# main_cj125.net
KiCad netlist of a schematic drawn in EAGLE
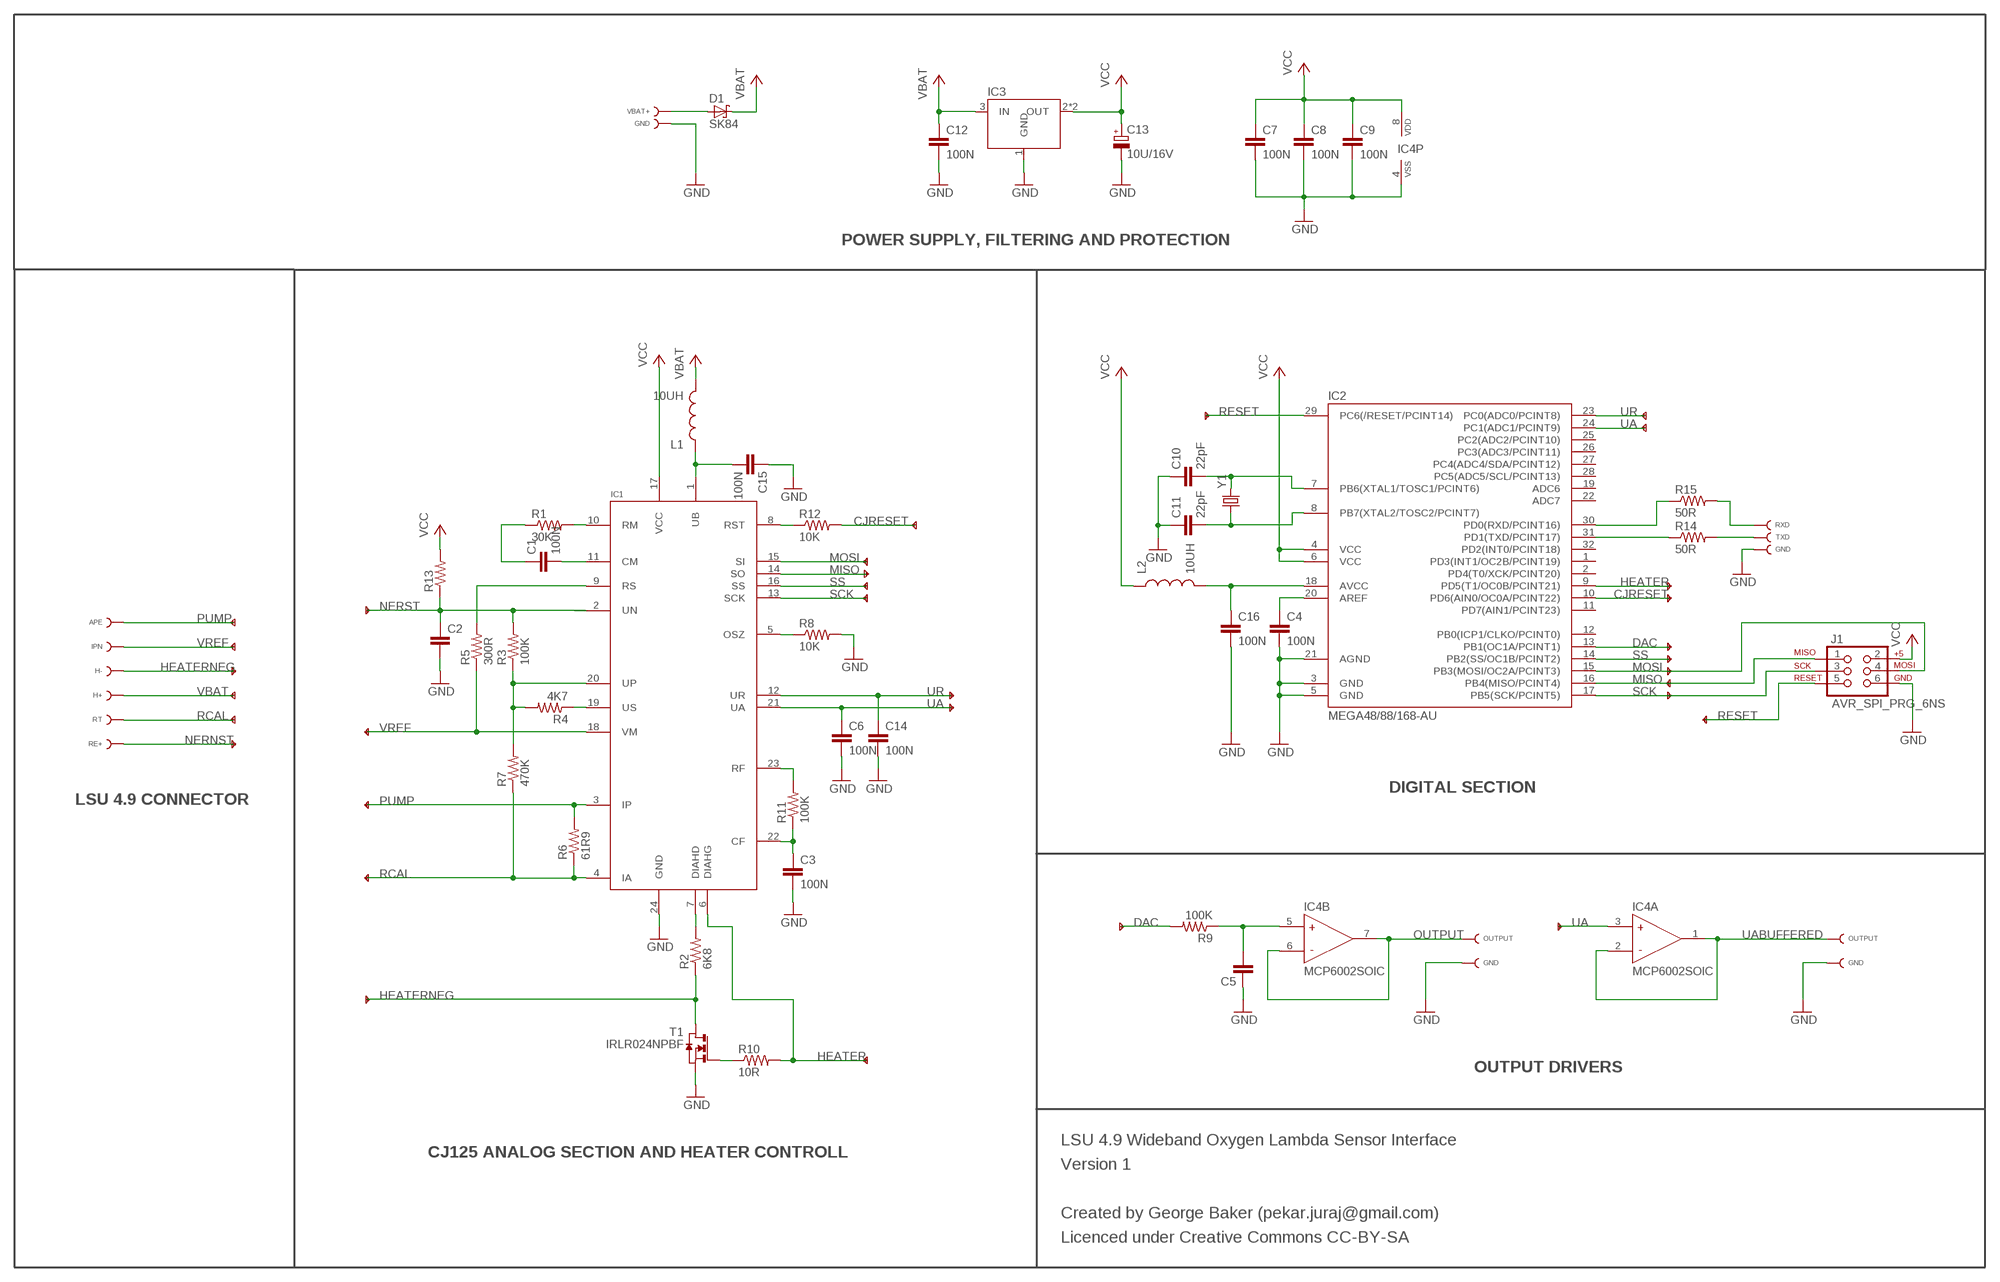
[diagram p0: schematic, sheet 1]

(export (version "E")
  (design (tool "Eeschema 10.0.6"))
  (components
    (comp (ref "C1")
      (value "100N")
      (footprint "eagle-import:0805")
      (libsource (lib "eagle-import") (part "CAP0805"))
    )
    (comp (ref "C2")
      (value "CAP0805")
      (footprint "eagle-import:0805")
      (libsource (lib "eagle-import") (part "CAP0805"))
    )
    (comp (ref "C3")
      (value "100N")
      (footprint "eagle-import:0805")
      (libsource (lib "eagle-import") (part "CAP0805"))
    )
    (comp (ref "C4")
      (value "100N")
      (footprint "eagle-import:0805")
      (libsource (lib "eagle-import") (part "CAP0805"))
    )
    (comp (ref "C5")
      (value "CAP0805")
      (footprint "eagle-import:0805")
      (libsource (lib "eagle-import") (part "CAP0805"))
    )
    (comp (ref "C6")
      (value "100N")
      (footprint "eagle-import:0805")
      (libsource (lib "eagle-import") (part "CAP0805"))
    )
    (comp (ref "C7")
      (value "100N")
      (footprint "eagle-import:0805")
      (libsource (lib "eagle-import") (part "CAP0805"))
    )
    (comp (ref "C8")
      (value "100N")
      (footprint "eagle-import:0805")
      (libsource (lib "eagle-import") (part "CAP0805"))
    )
    (comp (ref "C9")
      (value "100N")
      (footprint "eagle-import:0805")
      (libsource (lib "eagle-import") (part "CAP0805"))
    )
    (comp (ref "C10")
      (value "22pF")
      (footprint "eagle-import:0805")
      (libsource (lib "eagle-import") (part "CAP0805"))
    )
    (comp (ref "C11")
      (value "22pF")
      (footprint "eagle-import:0805")
      (libsource (lib "eagle-import") (part "CAP0805"))
    )
    (comp (ref "C12")
      (value "100N")
      (footprint "eagle-import:0805")
      (libsource (lib "eagle-import") (part "CAP0805"))
    )
    (comp (ref "C13")
      (value "10U/16V")
      (footprint "eagle-import:SMC_A")
      (libsource (lib "eagle-import") (part "CPOL-EUSMCA"))
    )
    (comp (ref "C14")
      (value "100N")
      (footprint "eagle-import:0805")
      (libsource (lib "eagle-import") (part "CAP0805"))
    )
    (comp (ref "C15")
      (value "100N")
      (footprint "eagle-import:0805")
      (libsource (lib "eagle-import") (part "CAP0805"))
    )
    (comp (ref "C16")
      (value "100N")
      (footprint "eagle-import:0805")
      (libsource (lib "eagle-import") (part "CAP0805"))
    )
    (comp (ref "D1")
      (value "SK84")
      (footprint "eagle-import:SMC")
      (libsource (lib "eagle-import") (part "SCHOTTKY-DIODESMC"))
    )
    (comp (ref "IC1")
      (value "CJ125_SOIC24")
      (footprint "eagle-import:SO24W")
      (libsource (lib "eagle-import") (part "CJ125_SOIC24"))
    )
    (comp (ref "IC2")
      (value "MEGA48/88/168-AU")
      (footprint "eagle-import:TQFP32-08")
      (libsource (lib "eagle-import") (part "MEGA48/88/168-AU"))
    )
    (comp (ref "IC3")
      (value "REG1117_SOT-223")
      (footprint "eagle-import:SOT223")
      (libsource (lib "eagle-import") (part "REG1117_SOT-223"))
    )
    (comp (ref "IC4")
      (value "MCP6002SOIC")
      (footprint "eagle-import:SO8")
      (libsource (lib "eagle-import") (part "MCP6002SOIC"))
    )
    (comp (ref "J1")
      (value "AVR_SPI_PRG_6NS")
      (footprint "eagle-import:2X3-NS")
      (libsource (lib "eagle-import") (part "AVR_SPI_PRG_6NS"))
    )
    (comp (ref "L1")
      (value "10UH")
      (footprint "eagle-import:0805")
      (libsource (lib "eagle-import") (part "INDUCTOR0805"))
    )
    (comp (ref "L2")
      (value "10UH")
      (footprint "eagle-import:0805")
      (libsource (lib "eagle-import") (part "INDUCTOR0805"))
    )
    (comp (ref "PAD1")
      (value "APE")
      (footprint "eagle-import:CONPAD-DUAL-HOLE-1.5MM")
      (libsource (lib "eagle-import") (part "CONPAD-DUAL-HOLE-1.5MM"))
    )
    (comp (ref "PAD2")
      (value "IPN")
      (footprint "eagle-import:CONPAD-DUAL-HOLE-1.5MM")
      (libsource (lib "eagle-import") (part "CONPAD-DUAL-HOLE-1.5MM"))
    )
    (comp (ref "PAD3")
      (value "H-")
      (footprint "eagle-import:CONPAD-DUAL-HOLE-1.5MM")
      (libsource (lib "eagle-import") (part "CONPAD-DUAL-HOLE-1.5MM"))
    )
    (comp (ref "PAD4")
      (value "H+")
      (footprint "eagle-import:CONPAD-DUAL-HOLE-1.5MM")
      (libsource (lib "eagle-import") (part "CONPAD-DUAL-HOLE-1.5MM"))
    )
    (comp (ref "PAD5")
      (value "RT")
      (footprint "eagle-import:CONPAD-DUAL-HOLE-1.5MM")
      (libsource (lib "eagle-import") (part "CONPAD-DUAL-HOLE-1.5MM"))
    )
    (comp (ref "PAD6")
      (value "RE+")
      (footprint "eagle-import:CONPAD-DUAL-HOLE-1.5MM")
      (libsource (lib "eagle-import") (part "CONPAD-DUAL-HOLE-1.5MM"))
    )
    (comp (ref "PAD7")
      (value "VBAT+")
      (footprint "eagle-import:CONPAD-DUAL-HOLE-1.5MM")
      (libsource (lib "eagle-import") (part "CONPAD-DUAL-HOLE-1.5MM"))
    )
    (comp (ref "PAD8")
      (value "GND")
      (footprint "eagle-import:CONPAD-DUAL-HOLE-1.5MM")
      (libsource (lib "eagle-import") (part "CONPAD-DUAL-HOLE-1.5MM"))
    )
    (comp (ref "PAD9")
      (value "RXD")
      (footprint "eagle-import:CONPAD-DUAL-HOLE-1.5MM")
      (libsource (lib "eagle-import") (part "CONPAD-DUAL-HOLE-1.5MM"))
    )
    (comp (ref "PAD10")
      (value "TXD")
      (footprint "eagle-import:CONPAD-DUAL-HOLE-1.5MM")
      (libsource (lib "eagle-import") (part "CONPAD-DUAL-HOLE-1.5MM"))
    )
    (comp (ref "PAD11")
      (value "GND")
      (footprint "eagle-import:CONPAD-DUAL-HOLE-1.5MM")
      (libsource (lib "eagle-import") (part "CONPAD-DUAL-HOLE-1.5MM"))
    )
    (comp (ref "PAD12")
      (value "OUTPUT")
      (footprint "eagle-import:CONPAD-DUAL-HOLE-1.5MM")
      (libsource (lib "eagle-import") (part "CONPAD-DUAL-HOLE-1.5MM"))
    )
    (comp (ref "PAD13")
      (value "GND")
      (footprint "eagle-import:CONPAD-DUAL-HOLE-1.5MM")
      (libsource (lib "eagle-import") (part "CONPAD-DUAL-HOLE-1.5MM"))
    )
    (comp (ref "PAD14")
      (value "OUTPUT")
      (footprint "eagle-import:CONPAD-DUAL-HOLE-1.5MM")
      (libsource (lib "eagle-import") (part "CONPAD-DUAL-HOLE-1.5MM"))
    )
    (comp (ref "PAD15")
      (value "GND")
      (footprint "eagle-import:CONPAD-DUAL-HOLE-1.5MM")
      (libsource (lib "eagle-import") (part "CONPAD-DUAL-HOLE-1.5MM"))
    )
    (comp (ref "R1")
      (value "30K")
      (footprint "eagle-import:0805")
      (libsource (lib "eagle-import") (part "RESISTOR0805-RES"))
    )
    (comp (ref "R2")
      (value "6K8")
      (footprint "eagle-import:0805")
      (libsource (lib "eagle-import") (part "RESISTOR0805-RES"))
    )
    (comp (ref "R3")
      (value "100K")
      (footprint "eagle-import:0805")
      (libsource (lib "eagle-import") (part "RESISTOR0805-RES"))
    )
    (comp (ref "R4")
      (value "4K7")
      (footprint "eagle-import:0805")
      (libsource (lib "eagle-import") (part "RESISTOR0805-RES"))
    )
    (comp (ref "R5")
      (value "300R")
      (footprint "eagle-import:0805")
      (libsource (lib "eagle-import") (part "RESISTOR0805-RES"))
    )
    (comp (ref "R6")
      (value "61R9")
      (footprint "eagle-import:0805")
      (libsource (lib "eagle-import") (part "RESISTOR0805-RES"))
    )
    (comp (ref "R7")
      (value "470K")
      (footprint "eagle-import:0805")
      (libsource (lib "eagle-import") (part "RESISTOR0805-RES"))
    )
    (comp (ref "R8")
      (value "10K")
      (footprint "eagle-import:0805")
      (libsource (lib "eagle-import") (part "RESISTOR0805-RES"))
    )
    (comp (ref "R9")
      (value "100K")
      (footprint "eagle-import:0805")
      (libsource (lib "eagle-import") (part "RESISTOR0805-RES"))
    )
    (comp (ref "R10")
      (value "10R")
      (footprint "eagle-import:0805")
      (libsource (lib "eagle-import") (part "RESISTOR0805-RES"))
    )
    (comp (ref "R11")
      (value "100K")
      (footprint "eagle-import:0805")
      (libsource (lib "eagle-import") (part "RESISTOR0805-RES"))
    )
    (comp (ref "R12")
      (value "10K")
      (footprint "eagle-import:0805")
      (libsource (lib "eagle-import") (part "RESISTOR0805-RES"))
    )
    (comp (ref "R13")
      (value "RESISTOR0805-RES")
      (footprint "eagle-import:0805")
      (libsource (lib "eagle-import") (part "RESISTOR0805-RES"))
    )
    (comp (ref "R14")
      (value "50R")
      (footprint "eagle-import:0805")
      (libsource (lib "eagle-import") (part "RESISTOR0805-RES"))
    )
    (comp (ref "R15")
      (value "50R")
      (footprint "eagle-import:0805")
      (libsource (lib "eagle-import") (part "RESISTOR0805-RES"))
    )
    (comp (ref "T1")
      (value "IRLR024NPBF")
      (footprint "eagle-import:TO252")
      (libsource (lib "eagle-import") (part "NMOSFET_TO252"))
    )
    (comp (ref "Y1")
      (value "CRYSTAL_ILCX13")
      (footprint "eagle-import:CRYSTAL_ILCX13")
      (libsource (lib "eagle-import") (part "CRYSTAL_ILCX13"))
    )
  )
  (nets
    (net (code "1") (name "/CJRESET") (class "Default")
      (node (ref "IC2") (pin "10") (pinfunction "PD6(AIN0/OC0A/PCINT22)_10") (pintype "bidirectional"))
      (node (ref "R12") (pin "2") (pinfunction "2_2") (pintype "passive"))
    )
    (net (code "2") (name "/DAC") (class "Default")
      (node (ref "IC2") (pin "13") (pinfunction "PB1(OC1A/PCINT1)_13") (pintype "bidirectional"))
      (node (ref "R9") (pin "2") (pinfunction "2_2") (pintype "passive"))
    )
    (net (code "3") (name "/HEATER") (class "Default")
      (node (ref "IC1") (pin "6") (pinfunction "DIAHG_6") (pintype "input"))
      (node (ref "IC2") (pin "9") (pinfunction "PD5(T1/OC0B/PCINT21)_9") (pintype "bidirectional"))
      (node (ref "R10") (pin "2") (pinfunction "2_2") (pintype "passive"))
    )
    (net (code "4") (name "/HEATERNEG") (class "Default")
      (node (ref "PAD3") (pin "P$1@1") (pinfunction "P$1_P$1@1") (pintype "passive"))
      (node (ref "PAD3") (pin "P$1@2") (pinfunction "P$1_P$1@2") (pintype "passive"))
      (node (ref "R2") (pin "1") (pinfunction "1_1") (pintype "passive"))
      (node (ref "T1") (pin "3") (pinfunction "D_3") (pintype "passive"))
    )
    (net (code "5") (name "/MISO") (class "Default")
      (node (ref "IC1") (pin "14") (pinfunction "SO_14") (pintype "bidirectional"))
      (node (ref "IC2") (pin "16") (pinfunction "PB4(MISO/PCINT4)_16") (pintype "bidirectional"))
      (node (ref "J1") (pin "1") (pinfunction "1_1") (pintype "passive"))
    )
    (net (code "6") (name "/MOSI") (class "Default")
      (node (ref "IC1") (pin "15") (pinfunction "SI_15") (pintype "bidirectional"))
      (node (ref "IC2") (pin "15") (pinfunction "PB3(MOSI/OC2A/PCINT3)_15") (pintype "bidirectional"))
      (node (ref "J1") (pin "4") (pinfunction "4_4") (pintype "passive"))
    )
    (net (code "7") (name "/NERNST") (class "Default")
      (node (ref "PAD6") (pin "P$1@1") (pinfunction "P$1_P$1@1") (pintype "passive"))
      (node (ref "PAD6") (pin "P$1@2") (pinfunction "P$1_P$1@2") (pintype "passive"))
    )
    (net (code "8") (name "/NERST") (class "Default")
      (node (ref "C2") (pin "1") (pinfunction "1_1") (pintype "passive"))
      (node (ref "IC1") (pin "2") (pinfunction "UN_2") (pintype "bidirectional"))
      (node (ref "R13") (pin "1") (pinfunction "1_1") (pintype "passive"))
      (node (ref "R3") (pin "2") (pinfunction "2_2") (pintype "passive"))
    )
    (net (code "9") (name "/OUTPUT") (class "Default")
      (node (ref "IC4") (pin "6") (pinfunction "INV_6") (pintype "input"))
      (node (ref "IC4") (pin "7") (pinfunction "OUT_7") (pintype "output"))
      (node (ref "PAD12") (pin "P$1@1") (pinfunction "P$1_P$1@1") (pintype "passive"))
      (node (ref "PAD12") (pin "P$1@2") (pinfunction "P$1_P$1@2") (pintype "passive"))
    )
    (net (code "10") (name "/PUMP") (class "Default")
      (node (ref "IC1") (pin "3") (pinfunction "IP_3") (pintype "bidirectional"))
      (node (ref "PAD1") (pin "P$1@1") (pinfunction "P$1_P$1@1") (pintype "passive"))
      (node (ref "PAD1") (pin "P$1@2") (pinfunction "P$1_P$1@2") (pintype "passive"))
      (node (ref "R6") (pin "2") (pinfunction "2_2") (pintype "passive"))
    )
    (net (code "11") (name "/RCAL") (class "Default")
      (node (ref "IC1") (pin "4") (pinfunction "IA_4") (pintype "bidirectional"))
      (node (ref "PAD5") (pin "P$1@1") (pinfunction "P$1_P$1@1") (pintype "passive"))
      (node (ref "PAD5") (pin "P$1@2") (pinfunction "P$1_P$1@2") (pintype "passive"))
      (node (ref "R6") (pin "1") (pinfunction "1_1") (pintype "passive"))
      (node (ref "R7") (pin "1") (pinfunction "1_1") (pintype "passive"))
    )
    (net (code "12") (name "/RESET") (class "Default")
      (node (ref "IC2") (pin "29") (pinfunction "PC6(/RESET/PCINT14)_29") (pintype "bidirectional"))
      (node (ref "J1") (pin "5") (pinfunction "5_5") (pintype "passive"))
    )
    (net (code "13") (name "/SCK") (class "Default")
      (node (ref "IC1") (pin "13") (pinfunction "SCK_13") (pintype "bidirectional"))
      (node (ref "IC2") (pin "17") (pinfunction "PB5(SCK/PCINT5)_17") (pintype "bidirectional"))
      (node (ref "J1") (pin "3") (pinfunction "3_3") (pintype "passive"))
    )
    (net (code "14") (name "/SS") (class "Default")
      (node (ref "IC1") (pin "16") (pinfunction "SS_16") (pintype "bidirectional"))
      (node (ref "IC2") (pin "14") (pinfunction "PB2(SS/OC1B/PCINT2)_14") (pintype "bidirectional"))
    )
    (net (code "15") (name "/UA") (class "Default")
      (node (ref "C6") (pin "1") (pinfunction "1_1") (pintype "passive"))
      (node (ref "IC1") (pin "21") (pinfunction "UA_21") (pintype "bidirectional"))
      (node (ref "IC2") (pin "24") (pinfunction "PC1(ADC1/PCINT9)_24") (pintype "bidirectional"))
      (node (ref "IC4") (pin "3") (pinfunction "NONINV_3") (pintype "input"))
    )
    (net (code "16") (name "/UABUFFERED") (class "Default")
      (node (ref "IC4") (pin "1") (pinfunction "OUT_1") (pintype "output"))
      (node (ref "IC4") (pin "2") (pinfunction "INV_2") (pintype "input"))
      (node (ref "PAD14") (pin "P$1@1") (pinfunction "P$1_P$1@1") (pintype "passive"))
      (node (ref "PAD14") (pin "P$1@2") (pinfunction "P$1_P$1@2") (pintype "passive"))
    )
    (net (code "17") (name "/UR") (class "Default")
      (node (ref "C14") (pin "1") (pinfunction "1_1") (pintype "passive"))
      (node (ref "IC1") (pin "12") (pinfunction "UR_12") (pintype "bidirectional"))
      (node (ref "IC2") (pin "23") (pinfunction "PC0(ADC0/PCINT8)_23") (pintype "bidirectional"))
    )
    (net (code "18") (name "/VREF") (class "Default")
      (node (ref "IC1") (pin "18") (pinfunction "VM_18") (pintype "bidirectional"))
      (node (ref "PAD2") (pin "P$1@1") (pinfunction "P$1_P$1@1") (pintype "passive"))
      (node (ref "PAD2") (pin "P$1@2") (pinfunction "P$1_P$1@2") (pintype "passive"))
      (node (ref "R5") (pin "1") (pinfunction "1_1") (pintype "passive"))
    )
    (net (code "19") (name "GND") (class "Default")
      (node (ref "C10") (pin "1") (pinfunction "1_1") (pintype "passive"))
      (node (ref "C11") (pin "1") (pinfunction "1_1") (pintype "passive"))
      (node (ref "C12") (pin "2") (pinfunction "2_2") (pintype "passive"))
      (node (ref "C13") (pin "-") (pinfunction "-_-") (pintype "passive"))
      (node (ref "C14") (pin "2") (pinfunction "2_2") (pintype "passive"))
      (node (ref "C15") (pin "1") (pinfunction "1_1") (pintype "passive"))
      (node (ref "C16") (pin "2") (pinfunction "2_2") (pintype "passive"))
      (node (ref "C2") (pin "2") (pinfunction "2_2") (pintype "passive"))
      (node (ref "C3") (pin "2") (pinfunction "2_2") (pintype "passive"))
      (node (ref "C4") (pin "2") (pinfunction "2_2") (pintype "passive"))
      (node (ref "C5") (pin "1") (pinfunction "1_1") (pintype "passive"))
      (node (ref "C6") (pin "2") (pinfunction "2_2") (pintype "passive"))
      (node (ref "C7") (pin "2") (pinfunction "2_2") (pintype "passive"))
      (node (ref "C8") (pin "2") (pinfunction "2_2") (pintype "passive"))
      (node (ref "C9") (pin "2") (pinfunction "2_2") (pintype "passive"))
      (node (ref "IC1") (pin "24") (pinfunction "GND_24") (pintype "power_in"))
      (node (ref "IC2") (pin "21") (pinfunction "AGND_21") (pintype "power_in"))
      (node (ref "IC2") (pin "3") (pinfunction "GND_3") (pintype "power_in"))
      (node (ref "IC2") (pin "5") (pinfunction "GND_5") (pintype "power_in"))
      (node (ref "IC3") (pin "1") (pinfunction "GND_1") (pintype "bidirectional"))
      (node (ref "IC4") (pin "4") (pinfunction "VSS_4") (pintype "bidirectional"))
      (node (ref "J1") (pin "6") (pinfunction "6_6") (pintype "passive"))
      (node (ref "PAD11") (pin "P$1@1") (pinfunction "P$1_P$1@1") (pintype "passive"))
      (node (ref "PAD11") (pin "P$1@2") (pinfunction "P$1_P$1@2") (pintype "passive"))
      (node (ref "PAD13") (pin "P$1@1") (pinfunction "P$1_P$1@1") (pintype "passive"))
      (node (ref "PAD13") (pin "P$1@2") (pinfunction "P$1_P$1@2") (pintype "passive"))
      (node (ref "PAD15") (pin "P$1@1") (pinfunction "P$1_P$1@1") (pintype "passive"))
      (node (ref "PAD15") (pin "P$1@2") (pinfunction "P$1_P$1@2") (pintype "passive"))
      (node (ref "PAD8") (pin "P$1@1") (pinfunction "P$1_P$1@1") (pintype "passive"))
      (node (ref "PAD8") (pin "P$1@2") (pinfunction "P$1_P$1@2") (pintype "passive"))
      (node (ref "R8") (pin "2") (pinfunction "2_2") (pintype "passive"))
      (node (ref "T1") (pin "2") (pinfunction "S_2") (pintype "passive"))
    )
    (net (code "20") (name "Net-(C1-Pad1)") (class "Default")
      (node (ref "C1") (pin "1") (pinfunction "1_1") (pintype "passive"))
      (node (ref "R1") (pin "1") (pinfunction "1_1") (pintype "passive"))
    )
    (net (code "21") (name "Net-(D1-PadA)") (class "Default")
      (node (ref "D1") (pin "A") (pinfunction "A_A") (pintype "passive"))
      (node (ref "PAD7") (pin "P$1@1") (pinfunction "P$1_P$1@1") (pintype "passive"))
      (node (ref "PAD7") (pin "P$1@2") (pinfunction "P$1_P$1@2") (pintype "passive"))
    )
    (net (code "22") (name "Net-(IC1-CF)") (class "Default")
      (node (ref "C3") (pin "1") (pinfunction "1_1") (pintype "passive"))
      (node (ref "IC1") (pin "22") (pinfunction "CF_22") (pintype "bidirectional"))
      (node (ref "R11") (pin "1") (pinfunction "1_1") (pintype "passive"))
    )
    (net (code "23") (name "Net-(IC1-CM)") (class "Default")
      (node (ref "C1") (pin "2") (pinfunction "2_2") (pintype "passive"))
      (node (ref "IC1") (pin "11") (pinfunction "CM_11") (pintype "bidirectional"))
    )
    (net (code "24") (name "Net-(IC1-DIAHD)") (class "Default")
      (node (ref "IC1") (pin "7") (pinfunction "DIAHD_7") (pintype "input"))
      (node (ref "R2") (pin "2") (pinfunction "2_2") (pintype "passive"))
    )
    (net (code "25") (name "Net-(IC1-OSZ)") (class "Default")
      (node (ref "IC1") (pin "5") (pinfunction "OSZ_5") (pintype "bidirectional"))
      (node (ref "R8") (pin "1") (pinfunction "1_1") (pintype "passive"))
    )
    (net (code "26") (name "Net-(IC1-RF)") (class "Default")
      (node (ref "IC1") (pin "23") (pinfunction "RF_23") (pintype "bidirectional"))
      (node (ref "R11") (pin "2") (pinfunction "2_2") (pintype "passive"))
    )
    (net (code "27") (name "Net-(IC1-RM)") (class "Default")
      (node (ref "IC1") (pin "10") (pinfunction "RM_10") (pintype "bidirectional"))
      (node (ref "R1") (pin "2") (pinfunction "2_2") (pintype "passive"))
    )
    (net (code "28") (name "Net-(IC1-RS)") (class "Default")
      (node (ref "IC1") (pin "9") (pinfunction "RS_9") (pintype "bidirectional"))
      (node (ref "R5") (pin "2") (pinfunction "2_2") (pintype "passive"))
    )
    (net (code "29") (name "Net-(IC1-RST)") (class "Default")
      (node (ref "IC1") (pin "8") (pinfunction "RST_8") (pintype "bidirectional"))
      (node (ref "R12") (pin "1") (pinfunction "1_1") (pintype "passive"))
    )
    (net (code "30") (name "Net-(IC1-UB)") (class "Default")
      (node (ref "C15") (pin "2") (pinfunction "2_2") (pintype "passive"))
      (node (ref "IC1") (pin "1") (pinfunction "UB_1") (pintype "power_in"))
      (node (ref "L1") (pin "1") (pinfunction "1_1") (pintype "passive"))
    )
    (net (code "31") (name "Net-(IC1-UP)") (class "Default")
      (node (ref "IC1") (pin "20") (pinfunction "UP_20") (pintype "bidirectional"))
      (node (ref "R3") (pin "1") (pinfunction "1_1") (pintype "passive"))
      (node (ref "R4") (pin "2") (pinfunction "2_2") (pintype "passive"))
      (node (ref "R7") (pin "2") (pinfunction "2_2") (pintype "passive"))
    )
    (net (code "32") (name "Net-(IC1-US)") (class "Default")
      (node (ref "IC1") (pin "19") (pinfunction "US_19") (pintype "bidirectional"))
      (node (ref "R4") (pin "1") (pinfunction "1_1") (pintype "passive"))
    )
    (net (code "33") (name "Net-(IC2-AREF)") (class "Default")
      (node (ref "C4") (pin "1") (pinfunction "1_1") (pintype "passive"))
      (node (ref "IC2") (pin "20") (pinfunction "AREF_20") (pintype "passive"))
    )
    (net (code "34") (name "Net-(IC2-AVCC)") (class "Default")
      (node (ref "C16") (pin "1") (pinfunction "1_1") (pintype "passive"))
      (node (ref "IC2") (pin "18") (pinfunction "AVCC_18") (pintype "passive"))
      (node (ref "L2") (pin "2") (pinfunction "2_2") (pintype "passive"))
    )
    (net (code "35") (name "Net-(IC2-PB6(XTAL1{slash}TOSC1{slash}PCINT6))") (class "Default")
      (node (ref "C10") (pin "2") (pinfunction "2_2") (pintype "passive"))
      (node (ref "IC2") (pin "7") (pinfunction "PB6(XTAL1/TOSC1/PCINT6)_7") (pintype "bidirectional"))
      (node (ref "Y1") (pin "3") (pinfunction "2_3") (pintype "passive"))
    )
    (net (code "36") (name "Net-(IC2-PB7(XTAL2{slash}TOSC2{slash}PCINT7))") (class "Default")
      (node (ref "C11") (pin "2") (pinfunction "2_2") (pintype "passive"))
      (node (ref "IC2") (pin "8") (pinfunction "PB7(XTAL2/TOSC2/PCINT7)_8") (pintype "bidirectional"))
      (node (ref "Y1") (pin "1") (pinfunction "1_1") (pintype "passive"))
    )
    (net (code "37") (name "Net-(IC2-PD0(RXD{slash}PCINT16))") (class "Default")
      (node (ref "IC2") (pin "30") (pinfunction "PD0(RXD/PCINT16)_30") (pintype "bidirectional"))
      (node (ref "R15") (pin "1") (pinfunction "1_1") (pintype "passive"))
    )
    (net (code "38") (name "Net-(IC2-PD1(TXD{slash}PCINT17))") (class "Default")
      (node (ref "IC2") (pin "31") (pinfunction "PD1(TXD/PCINT17)_31") (pintype "bidirectional"))
      (node (ref "R14") (pin "1") (pinfunction "1_1") (pintype "passive"))
    )
    (net (code "39") (name "Net-(IC4B-NONINV)") (class "Default")
      (node (ref "C5") (pin "2") (pinfunction "2_2") (pintype "passive"))
      (node (ref "IC4") (pin "5") (pinfunction "NONINV_5") (pintype "input"))
      (node (ref "R9") (pin "1") (pinfunction "1_1") (pintype "passive"))
    )
    (net (code "40") (name "Net-(PAD9-P$1-PadP$1@1)") (class "Default")
      (node (ref "PAD9") (pin "P$1@1") (pinfunction "P$1_P$1@1") (pintype "passive"))
      (node (ref "PAD9") (pin "P$1@2") (pinfunction "P$1_P$1@2") (pintype "passive"))
      (node (ref "R15") (pin "2") (pinfunction "2_2") (pintype "passive"))
    )
    (net (code "41") (name "Net-(PAD10-P$1-PadP$1@1)") (class "Default")
      (node (ref "PAD10") (pin "P$1@1") (pinfunction "P$1_P$1@1") (pintype "passive"))
      (node (ref "PAD10") (pin "P$1@2") (pinfunction "P$1_P$1@2") (pintype "passive"))
      (node (ref "R14") (pin "2") (pinfunction "2_2") (pintype "passive"))
    )
    (net (code "42") (name "Net-(T1-G)") (class "Default")
      (node (ref "R10") (pin "1") (pinfunction "1_1") (pintype "passive"))
      (node (ref "T1") (pin "1") (pinfunction "G_1") (pintype "passive"))
    )
    (net (code "43") (name "VBAT") (class "Default")
      (node (ref "C12") (pin "1") (pinfunction "1_1") (pintype "passive"))
      (node (ref "D1") (pin "C") (pinfunction "C_C") (pintype "passive"))
      (node (ref "IC3") (pin "3") (pinfunction "IN_3") (pintype "power_in"))
      (node (ref "L1") (pin "2") (pinfunction "2_2") (pintype "passive"))
      (node (ref "PAD4") (pin "P$1@1") (pinfunction "P$1_P$1@1") (pintype "passive"))
      (node (ref "PAD4") (pin "P$1@2") (pinfunction "P$1_P$1@2") (pintype "passive"))
    )
    (net (code "44") (name "VCC") (class "Default")
      (node (ref "C13") (pin "+") (pinfunction "+_+") (pintype "passive"))
      (node (ref "C7") (pin "1") (pinfunction "1_1") (pintype "passive"))
      (node (ref "C8") (pin "1") (pinfunction "1_1") (pintype "passive"))
      (node (ref "C9") (pin "1") (pinfunction "1_1") (pintype "passive"))
      (node (ref "IC1") (pin "17") (pinfunction "VCC_17") (pintype "power_in"))
      (node (ref "IC2") (pin "4") (pinfunction "VCC_4") (pintype "power_in"))
      (node (ref "IC2") (pin "6") (pinfunction "VCC_6") (pintype "power_in"))
      (node (ref "IC3") (pin "2") (pinfunction "OUT_2") (pintype "power_in"))
      (node (ref "IC3") (pin "4") (pinfunction "OUT_4") (pintype "power_in"))
      (node (ref "IC4") (pin "8") (pinfunction "VDD_8") (pintype "bidirectional"))
      (node (ref "J1") (pin "2") (pinfunction "2_2") (pintype "passive"))
      (node (ref "L2") (pin "1") (pinfunction "1_1") (pintype "passive"))
      (node (ref "R13") (pin "2") (pinfunction "2_2") (pintype "passive"))
    )
    (net (code "45") (name "unconnected-(IC2-ADC6-Pad19)") (class "Default")
      (node (ref "IC2") (pin "19") (pinfunction "ADC6_19") (pintype "passive"))
    )
    (net (code "46") (name "unconnected-(IC2-ADC7-Pad22)") (class "Default")
      (node (ref "IC2") (pin "22") (pinfunction "ADC7_22") (pintype "passive"))
    )
    (net (code "47") (name "unconnected-(IC2-PB0(ICP1{slash}CLKO{slash}PCINT0)-Pad12)") (class "Default")
      (node (ref "IC2") (pin "12") (pinfunction "PB0(ICP1/CLKO/PCINT0)_12") (pintype "bidirectional"))
    )
    (net (code "48") (name "unconnected-(IC2-PC2(ADC2{slash}PCINT10)-Pad25)") (class "Default")
      (node (ref "IC2") (pin "25") (pinfunction "PC2(ADC2/PCINT10)_25") (pintype "bidirectional"))
    )
    (net (code "49") (name "unconnected-(IC2-PC3(ADC3{slash}PCINT11)-Pad26)") (class "Default")
      (node (ref "IC2") (pin "26") (pinfunction "PC3(ADC3/PCINT11)_26") (pintype "bidirectional"))
    )
    (net (code "50") (name "unconnected-(IC2-PC4(ADC4{slash}SDA{slash}PCINT12)-Pad27)") (class "Default")
      (node (ref "IC2") (pin "27") (pinfunction "PC4(ADC4/SDA/PCINT12)_27") (pintype "bidirectional"))
    )
    (net (code "51") (name "unconnected-(IC2-PC5(ADC5{slash}SCL{slash}PCINT13)-Pad28)") (class "Default")
      (node (ref "IC2") (pin "28") (pinfunction "PC5(ADC5/SCL/PCINT13)_28") (pintype "bidirectional"))
    )
    (net (code "52") (name "unconnected-(IC2-PD2(INT0{slash}PCINT18)-Pad32)") (class "Default")
      (node (ref "IC2") (pin "32") (pinfunction "PD2(INT0/PCINT18)_32") (pintype "bidirectional"))
    )
    (net (code "53") (name "unconnected-(IC2-PD3(INT1{slash}OC2B{slash}PCINT19)-Pad1)") (class "Default")
      (node (ref "IC2") (pin "1") (pinfunction "PD3(INT1/OC2B/PCINT19)_1") (pintype "bidirectional"))
    )
    (net (code "54") (name "unconnected-(IC2-PD4(T0{slash}XCK{slash}PCINT20)-Pad2)") (class "Default")
      (node (ref "IC2") (pin "2") (pinfunction "PD4(T0/XCK/PCINT20)_2") (pintype "bidirectional"))
    )
    (net (code "55") (name "unconnected-(IC2-PD7(AIN1{slash}PCINT23)-Pad11)") (class "Default")
      (node (ref "IC2") (pin "11") (pinfunction "PD7(AIN1/PCINT23)_11") (pintype "bidirectional"))
    )
  )
)
